# Vertap_Power.net
KiCad netlist of a schematic drawn in Altium Designer
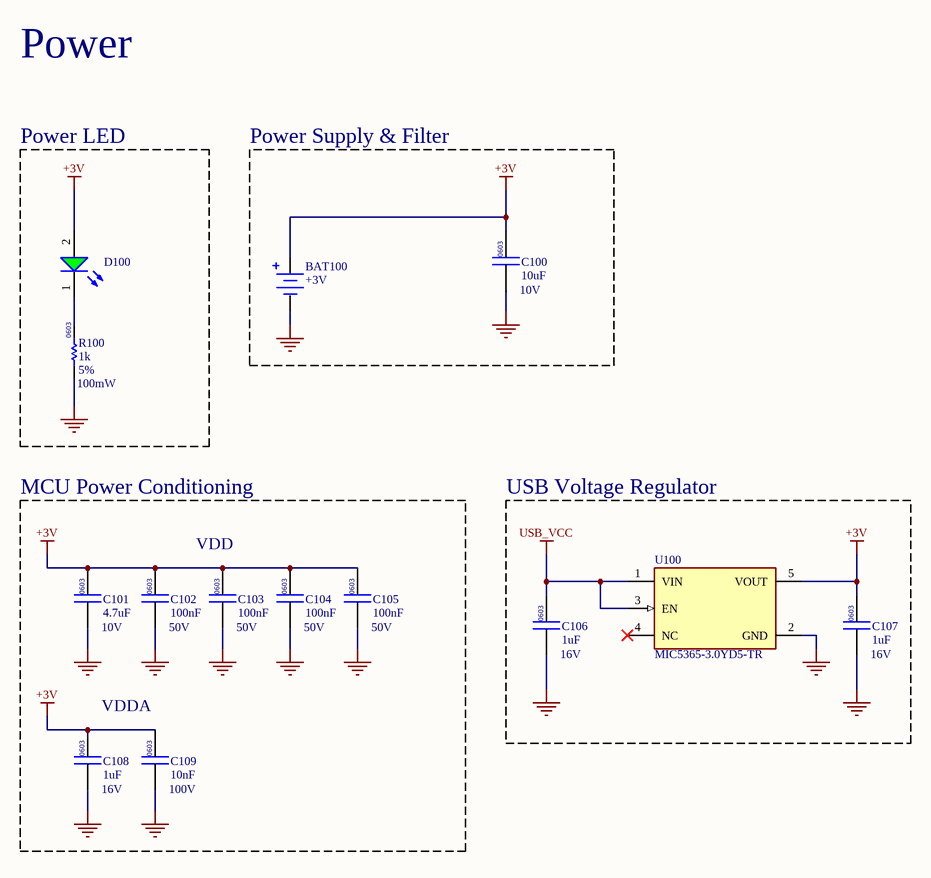
[diagram p0: Vertap_Power.SchDoc]

(export (version "E")
  (design (tool "Eeschema 10.0.6"))
  (components
    (comp (ref "BAT100")
      (value "+3V")
      (footprint "BH-67D-5")
      (description "BATT RETAINER COIN 20MM 1CEL SMD")
      (libsource (lib "Vertap_SchLib") (part "BH-67D-5"))
    )
    (comp (ref "C100")
      (value "10uF")
      (footprint "CAP_0603_MURATA")
      (description "CAP CER 10UF 10V X7R 0603")
      (libsource (lib "Vertap_SchLib") (part "CAP_10uF_0603"))
    )
    (comp (ref "C101")
      (value "4.7uF")
      (footprint "CAP_0603_MURATA")
      (description "CAP CER 4.7UF 10V X7R 0603")
      (libsource (lib "Vertap_SchLib") (part "CAP_4.7uF_0603"))
    )
    (comp (ref "C102")
      (value "100nF")
      (footprint "CAP_0603_MURATA")
      (description "CAP CER 0.1UF 50V X7R 0603")
      (libsource (lib "Vertap_SchLib") (part "CAP_0.1uF_0603"))
    )
    (comp (ref "C103")
      (value "100nF")
      (footprint "CAP_0603_MURATA")
      (description "CAP CER 0.1UF 50V X7R 0603")
      (libsource (lib "Vertap_SchLib") (part "CAP_0.1uF_0603"))
    )
    (comp (ref "C104")
      (value "100nF")
      (footprint "CAP_0603_MURATA")
      (description "CAP CER 0.1UF 50V X7R 0603")
      (libsource (lib "Vertap_SchLib") (part "CAP_0.1uF_0603"))
    )
    (comp (ref "C105")
      (value "100nF")
      (footprint "CAP_0603_MURATA")
      (description "CAP CER 0.1UF 50V X7R 0603")
      (libsource (lib "Vertap_SchLib") (part "CAP_0.1uF_0603"))
    )
    (comp (ref "C106")
      (value "1uF")
      (footprint "CAP_0603_MURATA")
      (description "CAP CER 1UF 16V X7R 0603")
      (libsource (lib "Vertap_SchLib") (part "CAP_1uF_0603"))
    )
    (comp (ref "C107")
      (value "1uF")
      (footprint "CAP_0603_MURATA")
      (description "CAP CER 1UF 16V X7R 0603")
      (libsource (lib "Vertap_SchLib") (part "CAP_1uF_0603"))
    )
    (comp (ref "C108")
      (value "1uF")
      (footprint "CAP_0603_MURATA")
      (description "CAP CER 1UF 16V X7R 0603")
      (libsource (lib "Vertap_SchLib") (part "CAP_1uF_0603"))
    )
    (comp (ref "C109")
      (value "10nF")
      (footprint "CAP_0603_MURATA")
      (description "CAP CER 10000PF 100V X7R 0603")
      (libsource (lib "Vertap_SchLib") (part "CAP_10nF_0603"))
    )
    (comp (ref "D100")
      (value "150060VS75000")
      (footprint "WL-SMCW_0603_150060xx75000")
      (libsource (lib "Altium Content Vault") (part "LED_Green_2A-1K"))
    )
    (comp (ref "R100")
      (value "1k")
      (footprint "RESC1608X55X25LL10T15")
      (fields (field (name "MANUFACTURER") "Yageo") (field (name "PART NUMBER") "RC0603JR-101KL"))
      (libsource (lib "Altium Content Vault") (part "RES"))
    )
    (comp (ref "U100")
      (value "MIC5365-3.0YD5-TR")
      (footprint "FP-TSOT-5LD-PL-1-MFG")
      (description "MIC5365-3.0YD5-TR LDO Regulator Pos 3V 0.15A 5-Pin TSOT-23 T/R")
      (libsource (lib "Altium Content Vault") (part "49efecb8457b62bbb278fcbf558b656"))
    )
  )
  (nets
    (net (code "1") (name "+3V") (class "Default")
      (node (ref "BAT100") (pin "2") (pinfunction "+_2") (pintype "passive"))
      (node (ref "C100") (pin "1") (pinfunction "1_1") (pintype "passive"))
      (node (ref "C101") (pin "1") (pinfunction "1_1") (pintype "passive"))
      (node (ref "C102") (pin "1") (pinfunction "1_1") (pintype "passive"))
      (node (ref "C103") (pin "1") (pinfunction "1_1") (pintype "passive"))
      (node (ref "C104") (pin "1") (pinfunction "1_1") (pintype "passive"))
      (node (ref "C105") (pin "1") (pinfunction "1_1") (pintype "passive"))
      (node (ref "C107") (pin "1") (pinfunction "1_1") (pintype "passive"))
      (node (ref "C108") (pin "2") (pinfunction "2_2") (pintype "passive"))
      (node (ref "C109") (pin "1") (pinfunction "1_1") (pintype "passive"))
      (node (ref "D100") (pin "2") (pinfunction "A_2") (pintype "passive"))
      (node (ref "U100") (pin "5") (pinfunction "VOUT_5") (pintype "passive"))
    )
    (net (code "2") (name "GND") (class "Default")
      (node (ref "BAT100") (pin "1") (pinfunction "-_1") (pintype "passive"))
      (node (ref "C100") (pin "2") (pinfunction "2_2") (pintype "passive"))
      (node (ref "C101") (pin "2") (pinfunction "2_2") (pintype "passive"))
      (node (ref "C102") (pin "2") (pinfunction "2_2") (pintype "passive"))
      (node (ref "C103") (pin "2") (pinfunction "2_2") (pintype "passive"))
      (node (ref "C104") (pin "2") (pinfunction "2_2") (pintype "passive"))
      (node (ref "C105") (pin "2") (pinfunction "2_2") (pintype "passive"))
      (node (ref "C106") (pin "2") (pinfunction "2_2") (pintype "passive"))
      (node (ref "C107") (pin "2") (pinfunction "2_2") (pintype "passive"))
      (node (ref "C108") (pin "1") (pinfunction "1_1") (pintype "passive"))
      (node (ref "C109") (pin "2") (pinfunction "2_2") (pintype "passive"))
      (node (ref "R100") (pin "1") (pinfunction "1_1") (pintype "passive"))
      (node (ref "U100") (pin "2") (pinfunction "GND_2") (pintype "power_in"))
    )
    (net (code "3") (name "Net-(D100-K)") (class "Default")
      (node (ref "D100") (pin "1") (pinfunction "K_1") (pintype "passive"))
      (node (ref "R100") (pin "2") (pinfunction "2_2") (pintype "passive"))
    )
    (net (code "4") (name "USB_VCC") (class "Default")
      (node (ref "C106") (pin "1") (pinfunction "1_1") (pintype "passive"))
      (node (ref "U100") (pin "1") (pinfunction "VIN_1") (pintype "power_in"))
      (node (ref "U100") (pin "3") (pinfunction "EN_3") (pintype "input"))
    )
    (net (code "5") (name "unconnected-(U100-NC-Pad4)") (class "Default")
      (node (ref "U100") (pin "4") (pinfunction "NC_4") (pintype "passive+no_connect"))
    )
  )
)
